# Printrboard-Pi-Link.net
KiCad netlist of a schematic drawn in EAGLE
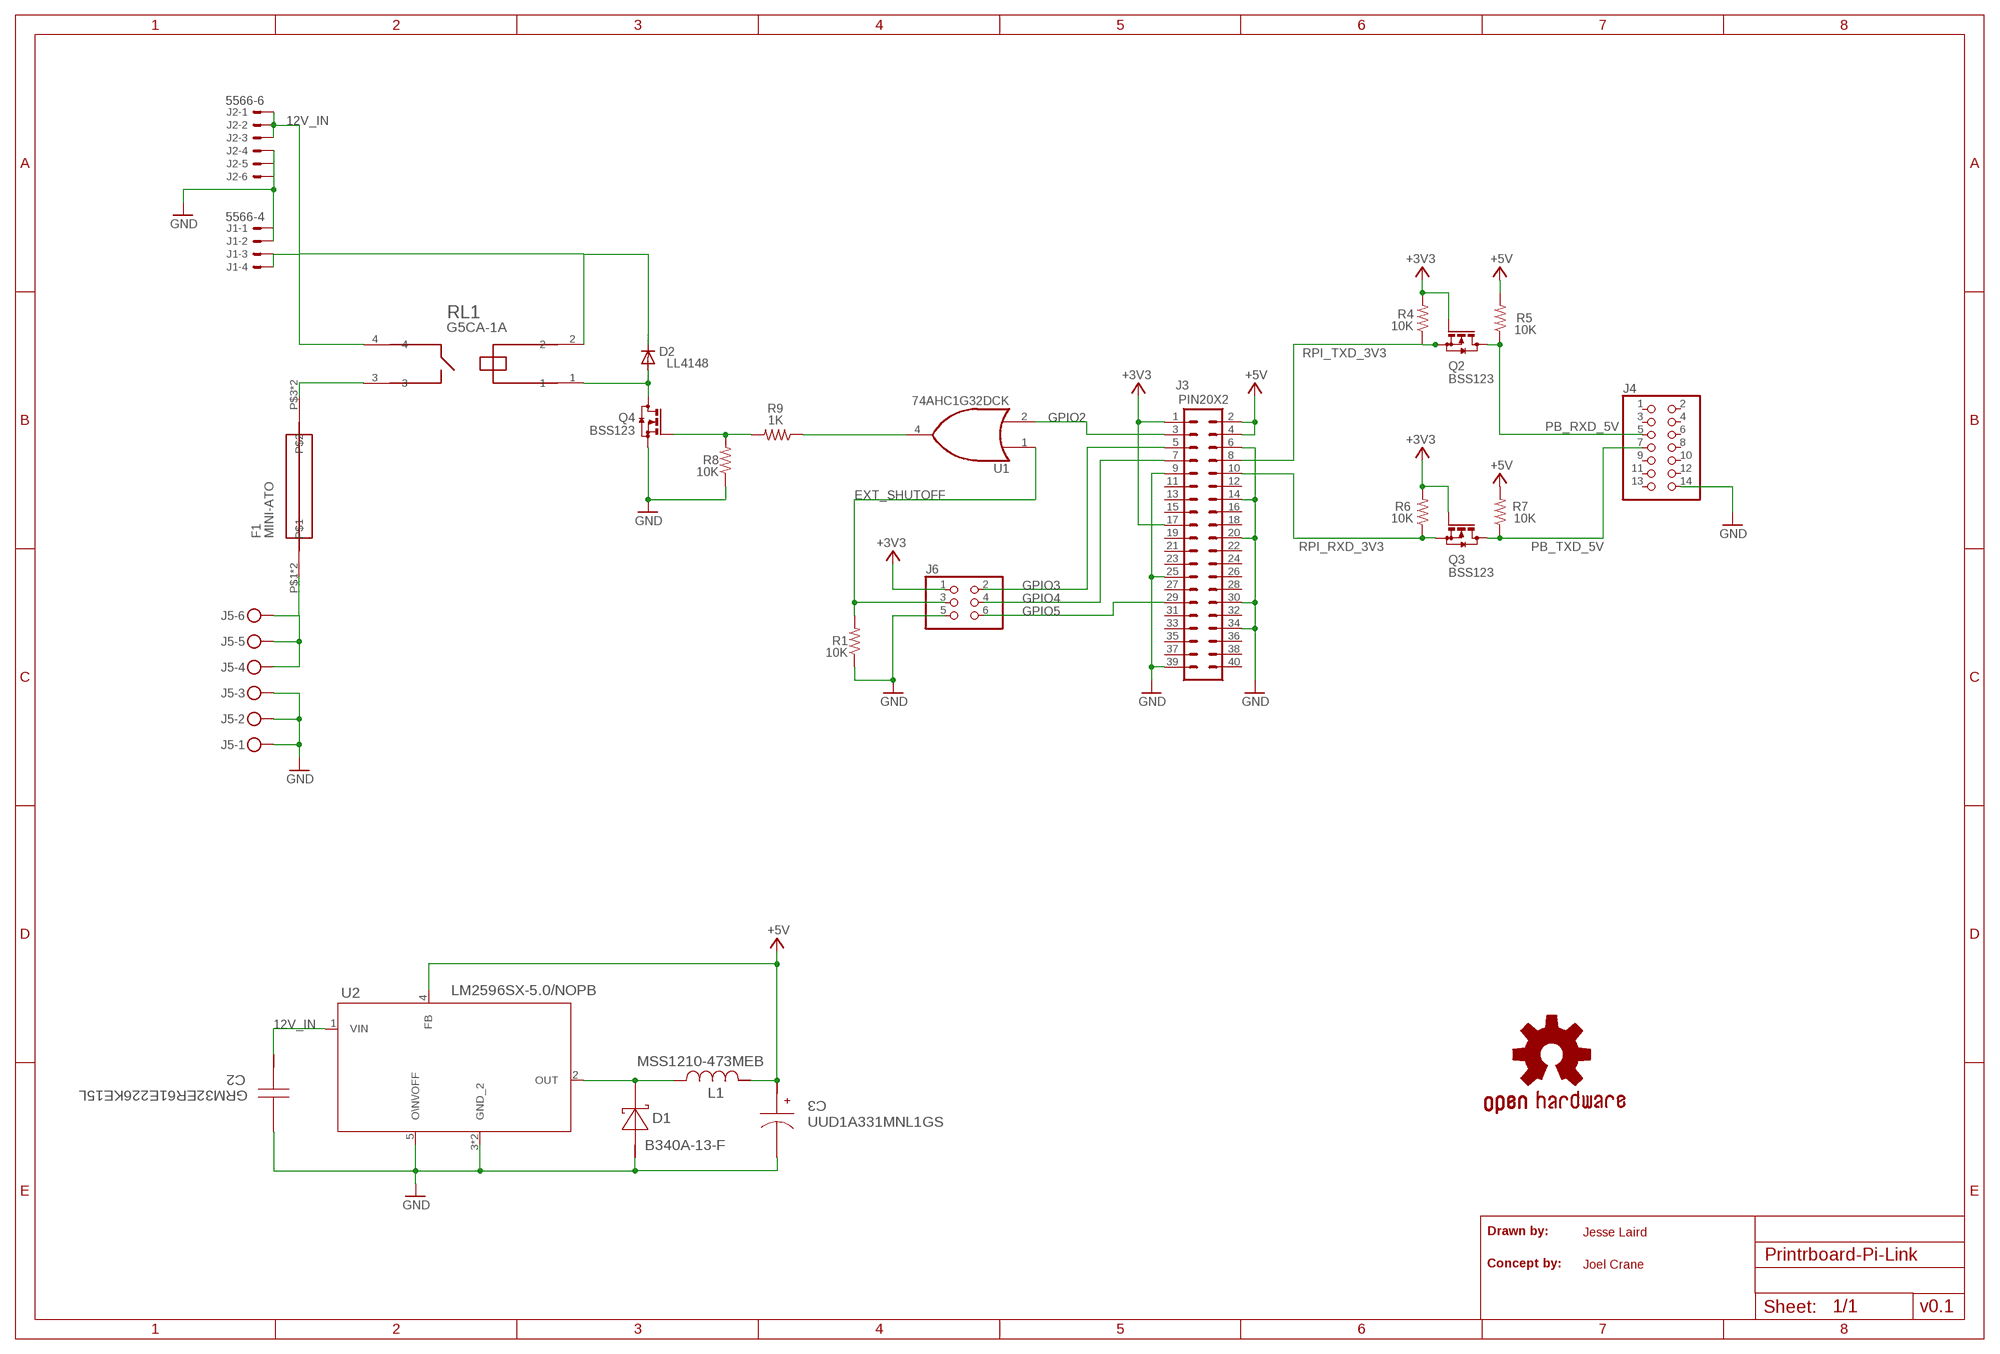
[diagram p0: schematic, sheet 1]

(export (version "E")
  (design (tool "Eeschema 10.0.6"))
  (components
    (comp (ref "C2")
      (value "GRM32ER61E226KE15L")
      (footprint "eagle-import:1210")
      (libsource (lib "eagle-import") (part "GRM32ER61E226KE15L"))
    )
    (comp (ref "C3")
      (value "UUD1A331MNL1GS")
      (footprint "eagle-import:SM_RADIAL_8MM")
      (libsource (lib "eagle-import") (part "UUD1A331MNL1GS"))
    )
    (comp (ref "D1")
      (value "B340A-13-F")
      (footprint "eagle-import:SMA")
      (libsource (lib "eagle-import") (part "B340A-13-F"))
    )
    (comp (ref "D2")
      (value "LL4148")
      (footprint "eagle-import:SOD80C")
      (libsource (lib "eagle-import") (part "PMLL4150"))
    )
    (comp (ref "F1")
      (value "MINI-ATO")
      (footprint "eagle-import:BK-6011")
      (libsource (lib "eagle-import") (part "MINI-ATO"))
    )
    (comp (ref "GOLD_ORB_SM1")
      (value "OSHWLOGO_GOLD_ORB_SM")
      (footprint "eagle-import:OSHW2")
      (libsource (lib "eagle-import") (part "OSHWLOGO_GOLD_ORB_SM"))
    )
    (comp (ref "J1")
      (value "5566-4")
      (footprint "eagle-import:5566-4")
      (libsource (lib "eagle-import") (part "5566-4"))
    )
    (comp (ref "J2")
      (value "5566-6")
      (footprint "eagle-import:5566-6")
      (fields (field (name "MPN") "95566-61002"))
      (libsource (lib "eagle-import") (part "5566-6"))
    )
    (comp (ref "J3")
      (value "PIN20X2")
      (footprint "eagle-import:PIN_20X2")
      (libsource (lib "eagle-import") (part "PIN20X2"))
    )
    (comp (ref "J4")
      (value "PINHD-2X7")
      (footprint "eagle-import:2X07")
      (libsource (lib "eagle-import") (part "PINHD-2X7"))
    )
    (comp (ref "J5")
      (value "MKDSN1,5/6-5,08")
      (footprint "eagle-import:MKDSN1,5_6-5,08")
      (libsource (lib "eagle-import") (part "MKDSN1,5/6-5,08"))
    )
    (comp (ref "J6")
      (value "PINHD-2X3")
      (footprint "eagle-import:2X03")
      (libsource (lib "eagle-import") (part "PINHD-2X3"))
    )
    (comp (ref "L1")
      (value "MSS1210-473MEB")
      (footprint "eagle-import:MSS1210")
      (fields (field (name "MANUFACTURER") "CoilCraft"))
      (libsource (lib "eagle-import") (part "MSS1210-473MEB"))
    )
    (comp (ref "Q2")
      (value "BSS123")
      (footprint "eagle-import:SOT23")
      (libsource (lib "eagle-import") (part "BSS123"))
    )
    (comp (ref "Q3")
      (value "BSS123")
      (footprint "eagle-import:SOT23")
      (libsource (lib "eagle-import") (part "BSS123"))
    )
    (comp (ref "Q4")
      (value "BSS123")
      (footprint "eagle-import:SOT23")
      (libsource (lib "eagle-import") (part "BSS123"))
    )
    (comp (ref "R1")
      (value "10K")
      (footprint "eagle-import:R0603")
      (libsource (lib "eagle-import") (part "R-US_R0603"))
    )
    (comp (ref "R4")
      (value "10K")
      (footprint "eagle-import:R0603")
      (libsource (lib "eagle-import") (part "R-US_R0603"))
    )
    (comp (ref "R5")
      (value "10K")
      (footprint "eagle-import:R0603")
      (libsource (lib "eagle-import") (part "R-US_R0603"))
    )
    (comp (ref "R6")
      (value "10K")
      (footprint "eagle-import:R0603")
      (libsource (lib "eagle-import") (part "R-US_R0603"))
    )
    (comp (ref "R7")
      (value "10K")
      (footprint "eagle-import:R0603")
      (libsource (lib "eagle-import") (part "R-US_R0603"))
    )
    (comp (ref "R8")
      (value "10K")
      (footprint "eagle-import:R0603")
      (libsource (lib "eagle-import") (part "R-US_R0603"))
    )
    (comp (ref "R9")
      (value "1K")
      (footprint "eagle-import:R0603")
      (libsource (lib "eagle-import") (part "R-US_R0603"))
    )
    (comp (ref "RL1")
      (value "G5CA-1A")
      (footprint "eagle-import:G5CA")
      (libsource (lib "eagle-import") (part "G5CA-1A"))
    )
    (comp (ref "U1")
      (value "74AHC1G32DCK")
      (footprint "eagle-import:SC70-5")
      (libsource (lib "eagle-import") (part "741G32DCKAHC"))
    )
    (comp (ref "U2")
      (value "LM2596SX-5.0/NOPB")
      (footprint "eagle-import:TS5B")
      (libsource (lib "eagle-import") (part "LM2596SX-5.0/NOPB"))
    )
  )
  (nets
    (net (code "1") (name "+3V3") (class "Default")
      (node (ref "J3") (pin "1") (pinfunction "1_1") (pintype "passive"))
      (node (ref "J3") (pin "17") (pinfunction "17_17") (pintype "passive"))
      (node (ref "J6") (pin "1") (pinfunction "1_1") (pintype "passive"))
      (node (ref "Q2") (pin "1") (pinfunction "G_1") (pintype "passive"))
      (node (ref "Q3") (pin "1") (pinfunction "G_1") (pintype "passive"))
      (node (ref "R4") (pin "2") (pinfunction "2_2") (pintype "passive"))
      (node (ref "R6") (pin "2") (pinfunction "2_2") (pintype "passive"))
    )
    (net (code "2") (name "+5V") (class "Default")
      (node (ref "C3") (pin "1") (pinfunction "+_1") (pintype "passive"))
      (node (ref "J3") (pin "2") (pinfunction "2_2") (pintype "passive"))
      (node (ref "J3") (pin "4") (pinfunction "4_4") (pintype "passive"))
      (node (ref "L1") (pin "2") (pinfunction "2_2") (pintype "passive"))
      (node (ref "R5") (pin "2") (pinfunction "2_2") (pintype "passive"))
      (node (ref "R7") (pin "2") (pinfunction "2_2") (pintype "passive"))
      (node (ref "U2") (pin "4") (pinfunction "FB_4") (pintype "passive"))
    )
    (net (code "3") (name "/12V_IN") (class "Default")
      (node (ref "C2") (pin "1") (pinfunction "1_1") (pintype "passive"))
      (node (ref "D2") (pin "C") (pinfunction "C_C") (pintype "passive"))
      (node (ref "J1") (pin "3") (pinfunction "S_3") (pintype "passive"))
      (node (ref "J1") (pin "4") (pinfunction "S_4") (pintype "passive"))
      (node (ref "J2") (pin "1") (pinfunction "S_1") (pintype "passive"))
      (node (ref "J2") (pin "2") (pinfunction "S_2") (pintype "passive"))
      (node (ref "J2") (pin "3") (pinfunction "S_3") (pintype "passive"))
      (node (ref "RL1") (pin "2") (pinfunction "2_2") (pintype "bidirectional"))
      (node (ref "RL1") (pin "4") (pinfunction "4_4") (pintype "bidirectional"))
      (node (ref "U2") (pin "1") (pinfunction "VIN_1") (pintype "passive"))
    )
    (net (code "4") (name "/EXT_SHUTOFF") (class "Default")
      (node (ref "J6") (pin "3") (pinfunction "3_3") (pintype "passive"))
      (node (ref "R1") (pin "2") (pinfunction "2_2") (pintype "passive"))
      (node (ref "U1") (pin "1") (pinfunction "I0_1") (pintype "input"))
    )
    (net (code "5") (name "/GPIO2") (class "Default")
      (node (ref "J3") (pin "3") (pinfunction "3_3") (pintype "passive"))
      (node (ref "U1") (pin "2") (pinfunction "I1_2") (pintype "input"))
    )
    (net (code "6") (name "/GPIO3") (class "Default")
      (node (ref "J3") (pin "5") (pinfunction "5_5") (pintype "passive"))
      (node (ref "J6") (pin "2") (pinfunction "2_2") (pintype "passive"))
    )
    (net (code "7") (name "/GPIO4") (class "Default")
      (node (ref "J3") (pin "7") (pinfunction "7_7") (pintype "passive"))
      (node (ref "J6") (pin "4") (pinfunction "4_4") (pintype "passive"))
    )
    (net (code "8") (name "/GPIO5") (class "Default")
      (node (ref "J3") (pin "29") (pinfunction "29_29") (pintype "passive"))
      (node (ref "J6") (pin "6") (pinfunction "6_6") (pintype "passive"))
    )
    (net (code "9") (name "/PB_RXD_5V") (class "Default")
      (node (ref "J4") (pin "5") (pinfunction "5_5") (pintype "passive"))
      (node (ref "Q2") (pin "3") (pinfunction "D_3") (pintype "passive"))
      (node (ref "R5") (pin "1") (pinfunction "1_1") (pintype "passive"))
    )
    (net (code "10") (name "/PB_TXD_5V") (class "Default")
      (node (ref "J4") (pin "7") (pinfunction "7_7") (pintype "passive"))
      (node (ref "Q3") (pin "3") (pinfunction "D_3") (pintype "passive"))
      (node (ref "R7") (pin "1") (pinfunction "1_1") (pintype "passive"))
    )
    (net (code "11") (name "/RPI_RXD_3V3") (class "Default")
      (node (ref "J3") (pin "10") (pinfunction "10_10") (pintype "passive"))
      (node (ref "Q3") (pin "2") (pinfunction "S_2") (pintype "passive"))
      (node (ref "R6") (pin "1") (pinfunction "1_1") (pintype "passive"))
    )
    (net (code "12") (name "/RPI_TXD_3V3") (class "Default")
      (node (ref "J3") (pin "8") (pinfunction "8_8") (pintype "passive"))
      (node (ref "Q2") (pin "2") (pinfunction "S_2") (pintype "passive"))
      (node (ref "R4") (pin "1") (pinfunction "1_1") (pintype "passive"))
    )
    (net (code "13") (name "GND") (class "Default")
      (node (ref "C2") (pin "2") (pinfunction "2_2") (pintype "passive"))
      (node (ref "C3") (pin "2") (pinfunction "-_2") (pintype "passive"))
      (node (ref "D1") (pin "2") (pinfunction "A_2") (pintype "passive"))
      (node (ref "J1") (pin "1") (pinfunction "S_1") (pintype "passive"))
      (node (ref "J1") (pin "2") (pinfunction "S_2") (pintype "passive"))
      (node (ref "J2") (pin "4") (pinfunction "S_4") (pintype "passive"))
      (node (ref "J2") (pin "5") (pinfunction "S_5") (pintype "passive"))
      (node (ref "J2") (pin "6") (pinfunction "S_6") (pintype "passive"))
      (node (ref "J3") (pin "14") (pinfunction "14_14") (pintype "passive"))
      (node (ref "J3") (pin "20") (pinfunction "20_20") (pintype "passive"))
      (node (ref "J3") (pin "25") (pinfunction "25_25") (pintype "passive"))
      (node (ref "J3") (pin "30") (pinfunction "30_30") (pintype "passive"))
      (node (ref "J3") (pin "34") (pinfunction "34_34") (pintype "passive"))
      (node (ref "J3") (pin "39") (pinfunction "39_39") (pintype "passive"))
      (node (ref "J3") (pin "6") (pinfunction "6_6") (pintype "passive"))
      (node (ref "J3") (pin "9") (pinfunction "9_9") (pintype "passive"))
      (node (ref "J4") (pin "14") (pinfunction "14_14") (pintype "passive"))
      (node (ref "J5") (pin "1") (pinfunction "KL_1") (pintype "passive"))
      (node (ref "J5") (pin "2") (pinfunction "KL_2") (pintype "passive"))
      (node (ref "J5") (pin "3") (pinfunction "KL_3") (pintype "passive"))
      (node (ref "J6") (pin "5") (pinfunction "5_5") (pintype "passive"))
      (node (ref "Q4") (pin "2") (pinfunction "S_2") (pintype "passive"))
      (node (ref "R1") (pin "1") (pinfunction "1_1") (pintype "passive"))
      (node (ref "R8") (pin "1") (pinfunction "1_1") (pintype "passive"))
      (node (ref "U2") (pin "3") (pinfunction "GND_2_3") (pintype "passive"))
      (node (ref "U2") (pin "5") (pinfunction "O\\N\\/OFF_5") (pintype "passive"))
      (node (ref "U2") (pin "6") (pinfunction "GND_2_6") (pintype "passive"))
    )
    (net (code "14") (name "Net-(D1-K)") (class "Default")
      (node (ref "D1") (pin "1") (pinfunction "K_1") (pintype "passive"))
      (node (ref "L1") (pin "1") (pinfunction "1_1") (pintype "passive"))
      (node (ref "U2") (pin "2") (pinfunction "OUT_2") (pintype "passive"))
    )
    (net (code "15") (name "Net-(F1-P$2-PadP$3)") (class "Default")
      (node (ref "F1") (pin "P$3") (pinfunction "P$2_P$3") (pintype "bidirectional"))
      (node (ref "F1") (pin "P$4") (pinfunction "P$2_P$4") (pintype "bidirectional"))
      (node (ref "RL1") (pin "3") (pinfunction "3_3") (pintype "bidirectional"))
    )
    (net (code "16") (name "Net-(J5D-KL)") (class "Default")
      (node (ref "F1") (pin "P$1") (pinfunction "P$1_P$1") (pintype "bidirectional"))
      (node (ref "F1") (pin "P$2") (pinfunction "P$1_P$2") (pintype "bidirectional"))
      (node (ref "J5") (pin "4") (pinfunction "KL_4") (pintype "passive"))
      (node (ref "J5") (pin "5") (pinfunction "KL_5") (pintype "passive"))
      (node (ref "J5") (pin "6") (pinfunction "KL_6") (pintype "passive"))
    )
    (net (code "17") (name "Net-(Q4-D)") (class "Default")
      (node (ref "D2") (pin "A") (pinfunction "A_A") (pintype "passive"))
      (node (ref "Q4") (pin "3") (pinfunction "D_3") (pintype "passive"))
      (node (ref "RL1") (pin "1") (pinfunction "1_1") (pintype "bidirectional"))
    )
    (net (code "18") (name "Net-(Q4-G)") (class "Default")
      (node (ref "Q4") (pin "1") (pinfunction "G_1") (pintype "passive"))
      (node (ref "R8") (pin "2") (pinfunction "2_2") (pintype "passive"))
      (node (ref "R9") (pin "2") (pinfunction "2_2") (pintype "passive"))
    )
    (net (code "19") (name "Net-(U1A-O)") (class "Default")
      (node (ref "R9") (pin "1") (pinfunction "1_1") (pintype "passive"))
      (node (ref "U1") (pin "4") (pinfunction "O_4") (pintype "output"))
    )
    (net (code "20") (name "unconnected-(J3-Pad11)") (class "Default")
      (node (ref "J3") (pin "11") (pinfunction "11_11") (pintype "passive"))
    )
    (net (code "21") (name "unconnected-(J3-Pad12)") (class "Default")
      (node (ref "J3") (pin "12") (pinfunction "12_12") (pintype "passive"))
    )
    (net (code "22") (name "unconnected-(J3-Pad13)") (class "Default")
      (node (ref "J3") (pin "13") (pinfunction "13_13") (pintype "passive"))
    )
    (net (code "23") (name "unconnected-(J3-Pad15)") (class "Default")
      (node (ref "J3") (pin "15") (pinfunction "15_15") (pintype "passive"))
    )
    (net (code "24") (name "unconnected-(J3-Pad16)") (class "Default")
      (node (ref "J3") (pin "16") (pinfunction "16_16") (pintype "passive"))
    )
    (net (code "25") (name "unconnected-(J3-Pad18)") (class "Default")
      (node (ref "J3") (pin "18") (pinfunction "18_18") (pintype "passive"))
    )
    (net (code "26") (name "unconnected-(J3-Pad19)") (class "Default")
      (node (ref "J3") (pin "19") (pinfunction "19_19") (pintype "passive"))
    )
    (net (code "27") (name "unconnected-(J3-Pad21)") (class "Default")
      (node (ref "J3") (pin "21") (pinfunction "21_21") (pintype "passive"))
    )
    (net (code "28") (name "unconnected-(J3-Pad22)") (class "Default")
      (node (ref "J3") (pin "22") (pinfunction "22_22") (pintype "passive"))
    )
    (net (code "29") (name "unconnected-(J3-Pad23)") (class "Default")
      (node (ref "J3") (pin "23") (pinfunction "23_23") (pintype "passive"))
    )
    (net (code "30") (name "unconnected-(J3-Pad24)") (class "Default")
      (node (ref "J3") (pin "24") (pinfunction "24_24") (pintype "passive"))
    )
    (net (code "31") (name "unconnected-(J3-Pad26)") (class "Default")
      (node (ref "J3") (pin "26") (pinfunction "26_26") (pintype "passive"))
    )
    (net (code "32") (name "unconnected-(J3-Pad27)") (class "Default")
      (node (ref "J3") (pin "27") (pinfunction "27_27") (pintype "passive"))
    )
    (net (code "33") (name "unconnected-(J3-Pad28)") (class "Default")
      (node (ref "J3") (pin "28") (pinfunction "28_28") (pintype "passive"))
    )
    (net (code "34") (name "unconnected-(J3-Pad31)") (class "Default")
      (node (ref "J3") (pin "31") (pinfunction "31_31") (pintype "passive"))
    )
    (net (code "35") (name "unconnected-(J3-Pad32)") (class "Default")
      (node (ref "J3") (pin "32") (pinfunction "32_32") (pintype "passive"))
    )
    (net (code "36") (name "unconnected-(J3-Pad33)") (class "Default")
      (node (ref "J3") (pin "33") (pinfunction "33_33") (pintype "passive"))
    )
    (net (code "37") (name "unconnected-(J3-Pad35)") (class "Default")
      (node (ref "J3") (pin "35") (pinfunction "35_35") (pintype "passive"))
    )
    (net (code "38") (name "unconnected-(J3-Pad36)") (class "Default")
      (node (ref "J3") (pin "36") (pinfunction "36_36") (pintype "passive"))
    )
    (net (code "39") (name "unconnected-(J3-Pad37)") (class "Default")
      (node (ref "J3") (pin "37") (pinfunction "37_37") (pintype "passive"))
    )
    (net (code "40") (name "unconnected-(J3-Pad38)") (class "Default")
      (node (ref "J3") (pin "38") (pinfunction "38_38") (pintype "passive"))
    )
    (net (code "41") (name "unconnected-(J3-Pad40)") (class "Default")
      (node (ref "J3") (pin "40") (pinfunction "40_40") (pintype "passive"))
    )
    (net (code "42") (name "unconnected-(J4-Pad1)") (class "Default")
      (node (ref "J4") (pin "1") (pinfunction "1_1") (pintype "passive"))
    )
    (net (code "43") (name "unconnected-(J4-Pad2)") (class "Default")
      (node (ref "J4") (pin "2") (pinfunction "2_2") (pintype "passive"))
    )
    (net (code "44") (name "unconnected-(J4-Pad3)") (class "Default")
      (node (ref "J4") (pin "3") (pinfunction "3_3") (pintype "passive"))
    )
    (net (code "45") (name "unconnected-(J4-Pad4)") (class "Default")
      (node (ref "J4") (pin "4") (pinfunction "4_4") (pintype "passive"))
    )
    (net (code "46") (name "unconnected-(J4-Pad6)") (class "Default")
      (node (ref "J4") (pin "6") (pinfunction "6_6") (pintype "passive"))
    )
    (net (code "47") (name "unconnected-(J4-Pad8)") (class "Default")
      (node (ref "J4") (pin "8") (pinfunction "8_8") (pintype "passive"))
    )
    (net (code "48") (name "unconnected-(J4-Pad9)") (class "Default")
      (node (ref "J4") (pin "9") (pinfunction "9_9") (pintype "passive"))
    )
    (net (code "49") (name "unconnected-(J4-Pad10)") (class "Default")
      (node (ref "J4") (pin "10") (pinfunction "10_10") (pintype "passive"))
    )
    (net (code "50") (name "unconnected-(J4-Pad11)") (class "Default")
      (node (ref "J4") (pin "11") (pinfunction "11_11") (pintype "passive"))
    )
    (net (code "51") (name "unconnected-(J4-Pad12)") (class "Default")
      (node (ref "J4") (pin "12") (pinfunction "12_12") (pintype "passive"))
    )
    (net (code "52") (name "unconnected-(J4-Pad13)") (class "Default")
      (node (ref "J4") (pin "13") (pinfunction "13_13") (pintype "passive"))
    )
  )
)
